# busanalizer.net
KiCad netlist of a schematic drawn in Altium Designer
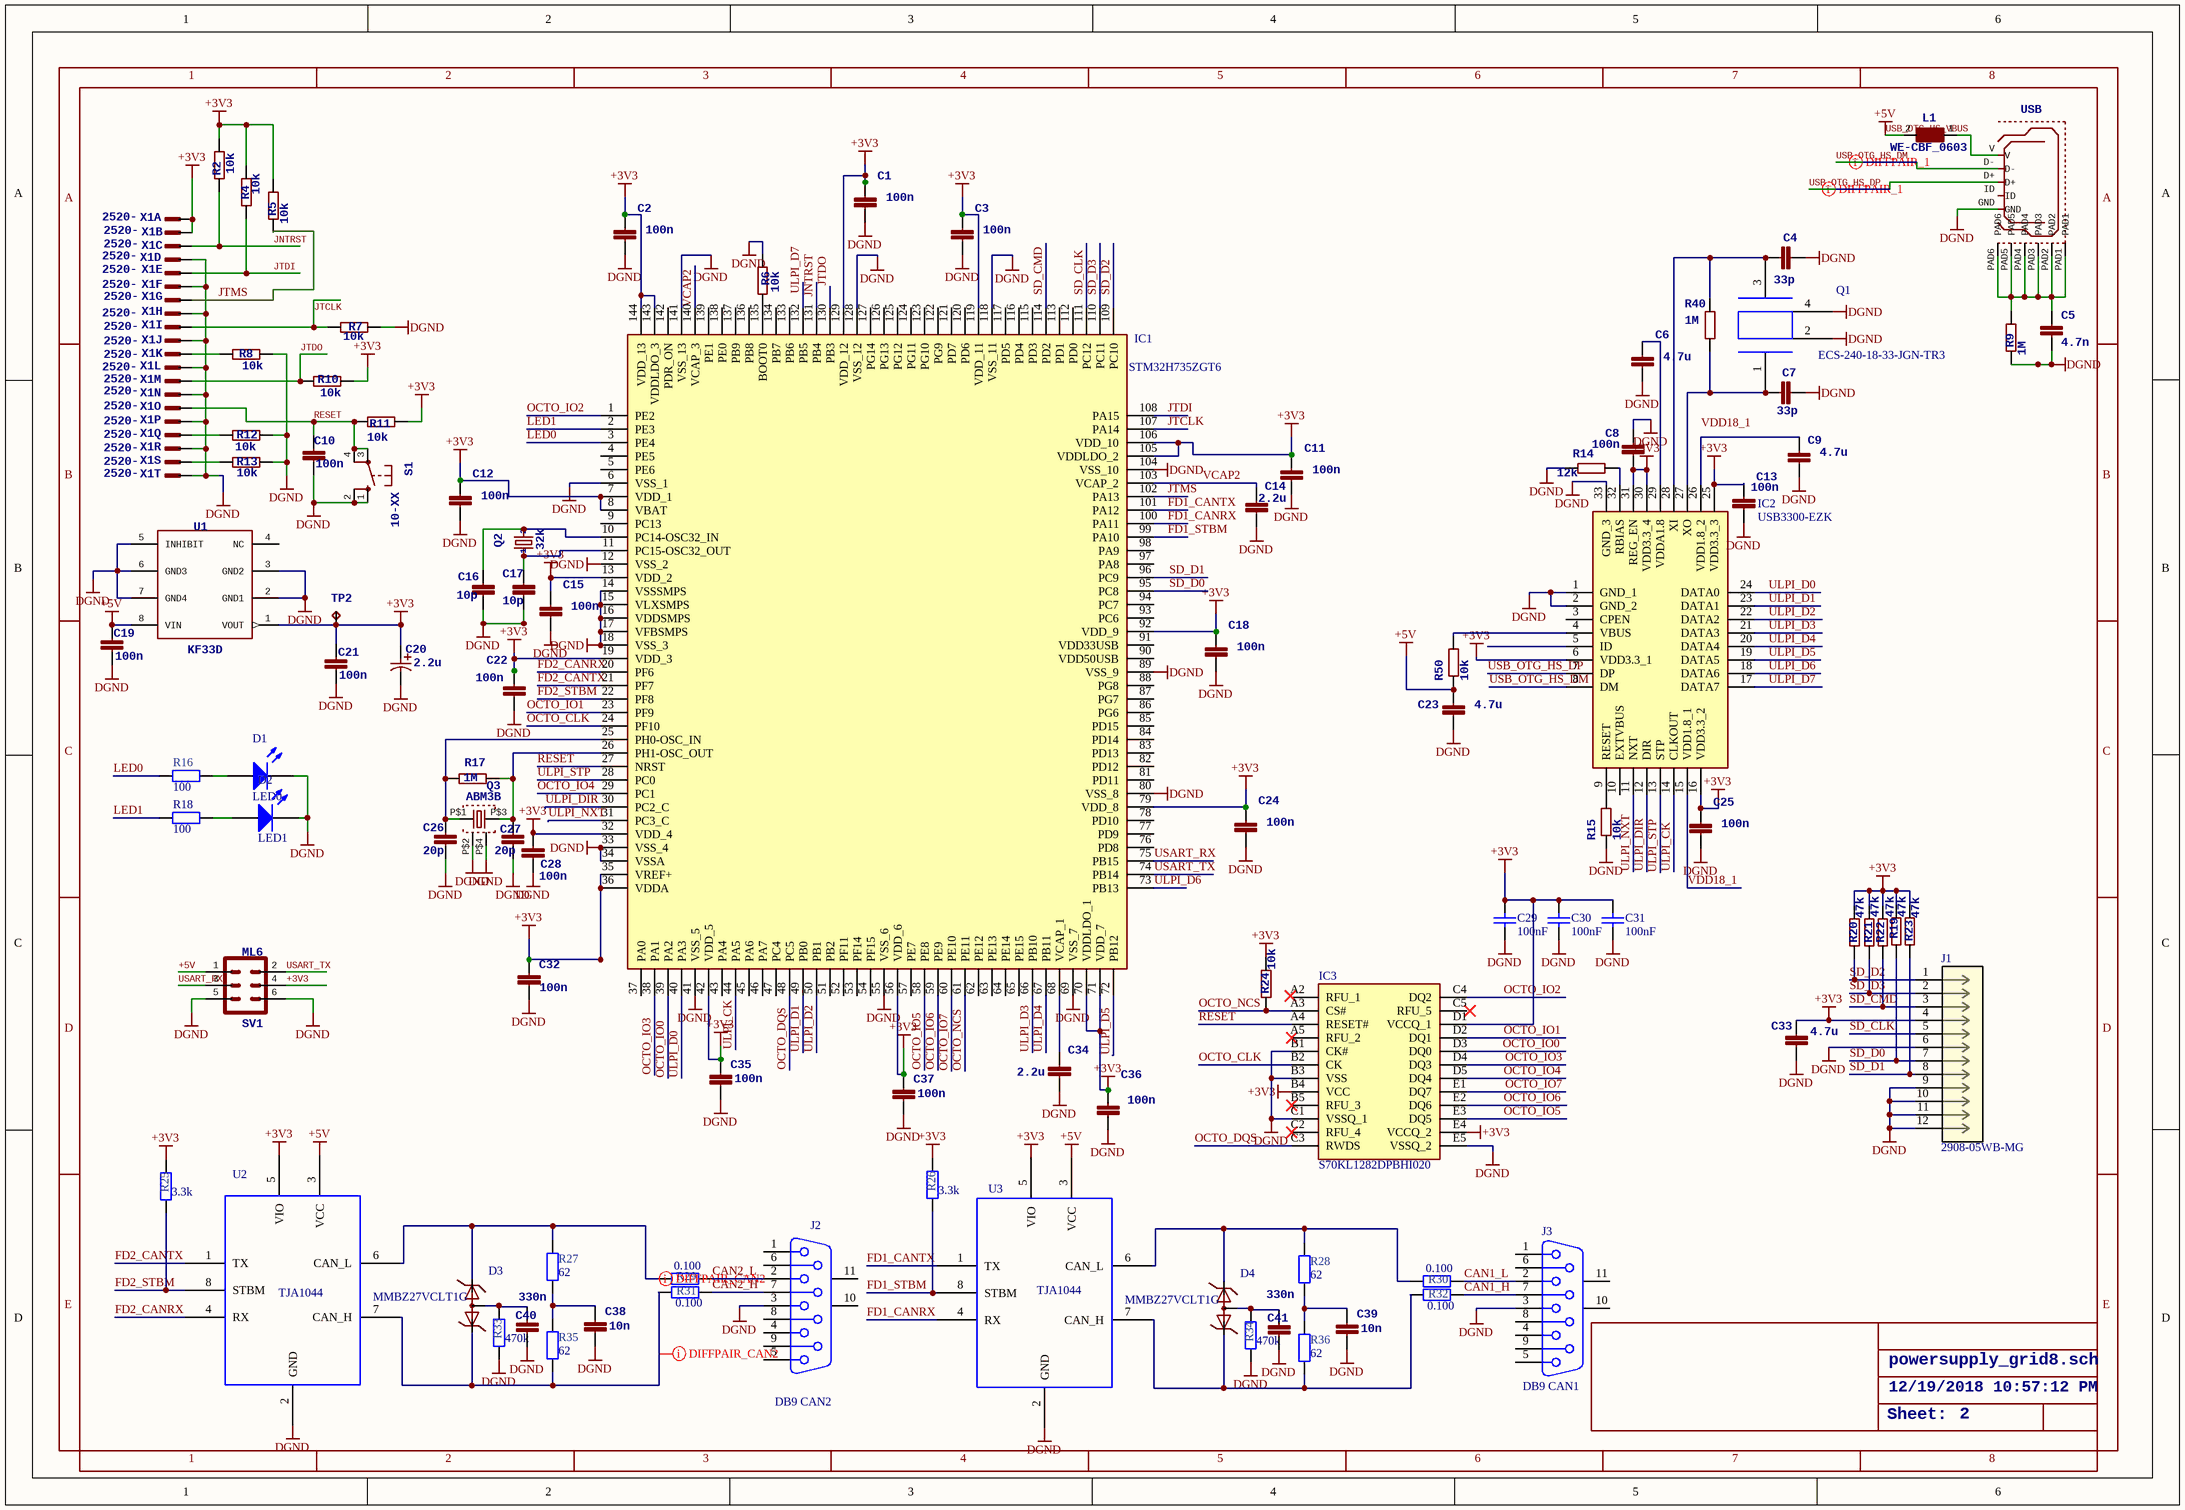
[diagram p0: busanalizer.SchDoc]

(export (version "E")
  (design (tool "Eeschema 10.0.6"))
  (components
    (comp (ref "C1")
      (value "100n")
      (footprint "C0402")
      (description "<B>CAPACITOR</B>, European symbol")
      (libsource (lib "rcl") (part "C-EUC0402"))
    )
    (comp (ref "C2")
      (value "100n")
      (footprint "C0402")
      (description "<B>CAPACITOR</B>, European symbol")
      (libsource (lib "rcl") (part "C-EUC0402"))
    )
    (comp (ref "C3")
      (value "100n")
      (footprint "C0402")
      (description "<B>CAPACITOR</B>, European symbol")
      (libsource (lib "rcl") (part "C-EUC0402"))
    )
    (comp (ref "C4")
      (value "33p")
      (footprint "C0402")
      (description "<B>CAPACITOR</B>, European symbol")
      (libsource (lib "") (part "C-EUC0402_1"))
    )
    (comp (ref "C5")
      (value "4.7n")
      (footprint "C0805")
      (description "<B>CAPACITOR</B>, European symbol")
      (libsource (lib "rcl") (part "C-EUC0805"))
    )
    (comp (ref "C6")
      (value "4.7u")
      (footprint "rcl:C0805")
      (description "<B>CAPACITOR</B>, European symbol")
      (libsource (lib "rcl") (part "C-EUC0402"))
    )
    (comp (ref "C7")
      (value "33p")
      (footprint "C0402")
      (description "<B>CAPACITOR</B>, European symbol")
      (libsource (lib "") (part "C-EUC0402_1"))
    )
    (comp (ref "C8")
      (value "100n")
      (footprint "C0402")
      (description "<B>CAPACITOR</B>, European symbol")
      (libsource (lib "") (part "C-EUC0402_2"))
    )
    (comp (ref "C9")
      (value "4.7u")
      (footprint "rcl:C0805")
      (description "<B>CAPACITOR</B>, European symbol")
      (libsource (lib "rcl") (part "C-EUC0402"))
    )
    (comp (ref "C10")
      (value "100n")
      (footprint "C0402")
      (description "<B>CAPACITOR</B>, European symbol")
      (libsource (lib "rcl") (part "C-EUC0402"))
    )
    (comp (ref "C11")
      (value "100n")
      (footprint "C0402")
      (description "<B>CAPACITOR</B>, European symbol")
      (libsource (lib "rcl") (part "C-EUC0402"))
    )
    (comp (ref "C12")
      (value "100n")
      (footprint "C0402")
      (description "<B>CAPACITOR</B>, European symbol")
      (libsource (lib "rcl") (part "C-EUC0402"))
    )
    (comp (ref "C13")
      (value "100n")
      (footprint "C0402")
      (description "<B>CAPACITOR</B>, European symbol")
      (libsource (lib "rcl") (part "C-EUC0402"))
    )
    (comp (ref "C14")
      (value "2.2u")
      (footprint "rcl:C0805")
      (description "<B>CAPACITOR</B>, European symbol")
      (libsource (lib "rcl") (part "C-EUC0402"))
    )
    (comp (ref "C15")
      (value "100n")
      (footprint "C0402")
      (description "<B>CAPACITOR</B>, European symbol")
      (libsource (lib "rcl") (part "C-EUC0402"))
    )
    (comp (ref "C16")
      (value "10p")
      (footprint "C0402")
      (description "<B>CAPACITOR</B>, European symbol")
      (libsource (lib "") (part "C-EUC0402_2"))
    )
    (comp (ref "C17")
      (value "10p")
      (footprint "C0402")
      (description "<B>CAPACITOR</B>, European symbol")
      (libsource (lib "") (part "C-EUC0402_2"))
    )
    (comp (ref "C18")
      (value "100n")
      (footprint "C0402")
      (description "<B>CAPACITOR</B>, European symbol")
      (libsource (lib "rcl") (part "C-EUC0402"))
    )
    (comp (ref "C19")
      (value "100n")
      (footprint "C0603")
      (description "<B>CAPACITOR</B>, European symbol")
      (libsource (lib "rcl") (part "C-EUC0603"))
    )
    (comp (ref "C20")
      (value "2.2u")
      (footprint "Panasonic-EEEFT_EEEH:CAPAE430X610N")
      (fields
        (field (name "MPN") "EEE-FT0J101AR")
        (field (name "TOLERANCE") "±20 %")
        (field (name "MPN_1") "EEE-FT1A680AR")
      )
      (libsource (lib "Panasonic-EEEFT_EEEH") (part "EEE--CASE-B"))
    )
    (comp (ref "C21")
      (value "100n")
      (footprint "C0603")
      (description "<B>CAPACITOR</B>, European symbol")
      (libsource (lib "rcl") (part "C-EUC0603"))
    )
    (comp (ref "C22")
      (value "100n")
      (footprint "C0402")
      (description "<B>CAPACITOR</B>, European symbol")
      (libsource (lib "rcl") (part "C-EUC0402"))
    )
    (comp (ref "C23")
      (value "4.7u")
      (footprint "rcl:C0805")
      (description "<B>CAPACITOR</B>, European symbol")
      (libsource (lib "rcl") (part "C-EUC0402"))
    )
    (comp (ref "C24")
      (value "100n")
      (footprint "C0402")
      (description "<B>CAPACITOR</B>, European symbol")
      (libsource (lib "rcl") (part "C-EUC0402"))
    )
    (comp (ref "C25")
      (value "100n")
      (footprint "C0402")
      (description "<B>CAPACITOR</B>, European symbol")
      (libsource (lib "rcl") (part "C-EUC0402"))
    )
    (comp (ref "C26")
      (value "20p")
      (footprint "C0402")
      (description "<B>CAPACITOR</B>, European symbol")
      (libsource (lib "rcl") (part "C-EUC0402"))
    )
    (comp (ref "C27")
      (value "20p")
      (footprint "C0402")
      (description "<B>CAPACITOR</B>, European symbol")
      (libsource (lib "rcl") (part "C-EUC0402"))
    )
    (comp (ref "C28")
      (value "100n")
      (footprint "C0402")
      (description "<B>CAPACITOR</B>, European symbol")
      (libsource (lib "rcl") (part "C-EUC0402"))
    )
    (comp (ref "C29")
      (value "100nF")
      (footprint "C0402")
      (description "Capacitor, MLCC, 100nF, 16V, X7R, 10%, 0402, T=0,5mm")
      (fields
        (field (name "INTERNAL_PART_NUMBER") "MCD-00102")
        (field (name "MANUFACTURER_PART_NUMBER") "CC0402KRX7R7BB104")
        (field (name "PROVIDED_BY") "SUBCO")
      )
      (libsource (lib "MCD_PARTS_database") (part "Capacitor"))
    )
    (comp (ref "C30")
      (value "100nF")
      (footprint "C0402")
      (description "Capacitor, MLCC, 100nF, 16V, X7R, 10%, 0402, T=0,5mm")
      (fields
        (field (name "INTERNAL_PART_NUMBER") "MCD-00102")
        (field (name "MANUFACTURER_PART_NUMBER") "CC0402KRX7R7BB104")
        (field (name "PROVIDED_BY") "SUBCO")
      )
      (libsource (lib "MCD_PARTS_database") (part "Capacitor"))
    )
    (comp (ref "C31")
      (value "100nF")
      (footprint "C0402")
      (description "Capacitor, MLCC, 100nF, 16V, X7R, 10%, 0402, T=0,5mm")
      (fields
        (field (name "INTERNAL_PART_NUMBER") "MCD-00102")
        (field (name "MANUFACTURER_PART_NUMBER") "CC0402KRX7R7BB104")
        (field (name "PROVIDED_BY") "SUBCO")
      )
      (libsource (lib "MCD_PARTS_database") (part "Capacitor"))
    )
    (comp (ref "C32")
      (value "100n")
      (footprint "C0402")
      (description "<B>CAPACITOR</B>, European symbol")
      (libsource (lib "rcl") (part "C-EUC0402"))
    )
    (comp (ref "C33")
      (value "4.7u")
      (footprint "rcl:C0805")
      (description "<B>CAPACITOR</B>, European symbol")
      (libsource (lib "rcl") (part "C-EUC0402"))
    )
    (comp (ref "C34")
      (value "2.2u")
      (footprint "rcl:C0805")
      (description "<B>CAPACITOR</B>, European symbol")
      (libsource (lib "rcl") (part "C-EUC0402"))
    )
    (comp (ref "C35")
      (value "100n")
      (footprint "C0402")
      (description "<B>CAPACITOR</B>, European symbol")
      (libsource (lib "rcl") (part "C-EUC0402"))
    )
    (comp (ref "C36")
      (value "100n")
      (footprint "C0402")
      (description "<B>CAPACITOR</B>, European symbol")
      (libsource (lib "rcl") (part "C-EUC0402"))
    )
    (comp (ref "C37")
      (value "100n")
      (footprint "C0402")
      (description "<B>CAPACITOR</B>, European symbol")
      (libsource (lib "rcl") (part "C-EUC0402"))
    )
    (comp (ref "C38")
      (value "10n")
      (footprint "C0805")
      (description "<B>CAPACITOR</B>, European symbol")
      (libsource (lib "rcl") (part "C-EUC0402"))
    )
    (comp (ref "C39")
      (value "10n")
      (footprint "C0805")
      (description "<B>CAPACITOR</B>, European symbol")
      (libsource (lib "rcl") (part "C-EUC0402"))
    )
    (comp (ref "C40")
      (value "330n")
      (footprint "C0805")
      (description "<B>CAPACITOR</B>, European symbol")
      (libsource (lib "rcl") (part "C-EUC0402"))
    )
    (comp (ref "C41")
      (value "330n")
      (footprint "C0805")
      (description "<B>CAPACITOR</B>, European symbol")
      (libsource (lib "rcl") (part "C-EUC0402"))
    )
    (comp (ref "D1")
      (value "LED0")
      (footprint "LED-0")
      (description "Typical INFRARED GaAs LED")
      (fields (field (name "PUBLISHER") "Altium Limited"))
      (libsource (lib "Miscellaneous Devices") (part "LED0"))
    )
    (comp (ref "D2")
      (value "LED1")
      (footprint "LED-0")
      (description "Typical INFRARED GaAs LED")
      (fields (field (name "PUBLISHER") "Altium Limited"))
      (libsource (lib "Miscellaneous Devices") (part "LED0"))
    )
    (comp (ref "D3")
      (value "MMBZ27VCLT1G")
      (footprint "SOT23")
      (libsource (lib "MMBZ27VCLT1G") (part "MMBZ27VCLT1G"))
    )
    (comp (ref "D4")
      (value "MMBZ27VCLT1G")
      (footprint "SOT23")
      (libsource (lib "MMBZ27VCLT1G") (part "MMBZ27VCLT1G"))
    )
    (comp (ref "IC1")
      (value "STM32H735ZGT6")
      (footprint "SamacSys:QFP50P2200X2200X160-144N")
      (description "Integrated Circuit")
      (libsource (lib "*") (part "STM32H735ZGT6"))
    )
    (comp (ref "IC2")
      (value "USB3300-EZK")
      (footprint "SamacSys:QFN50P500X500X100-33N-D")
      (description "Integrated Circuit")
      (fields (field (name "MOUSER2 PART NUMBER") "886-USB3300-EZK"))
      (libsource (lib "*") (part "USB3300-EZK"))
    )
    (comp (ref "IC3")
      (value "S70KL1282DPBHI020")
      (footprint "SamacSys:BGA24C100P5X5_600X800X100")
      (description "Integrated Circuit")
      (fields (field (name "MANUFACTURER_PART_NUMBER") "S70KL1281DABHI023"))
      (libsource (lib "*") (part "S70KL1281DABHI023"))
    )
    (comp (ref "J1")
      (value "2908-05WB-MG")
      (footprint "CONN_3M_2900")
      (description "No Description Available")
      (fields (field (name "COPYRIGHT") "Copyright (C) 2018 Accelerated Designs. All rights reserved"))
      (libsource (lib "2021-01-25_15-19-21") (part "2908-05WB-MG"))
    )
    (comp (ref "J2")
      (value "DB9 CAN2")
      (footprint "DSUB1.385-2H9")
      (description "Receptacle Assembly, 9 Position, Right Angle")
      (fields (field (name "PUBLISHER") "Altium Limited"))
      (libsource (lib "Miscellaneous Connectors") (part "D Connector 9"))
    )
    (comp (ref "J3")
      (value "DB9 CAN1")
      (footprint "DSUB1.385-2H9")
      (description "Receptacle Assembly, 9 Position, Right Angle")
      (fields (field (name "PUBLISHER") "Altium Limited"))
      (libsource (lib "Miscellaneous Connectors") (part "D Connector 9"))
    )
    (comp (ref "L1")
      (value "WE-CBF_0603")
      (footprint "WE-CBF:0603")
      (fields (field (name "MPN") "742792695"))
      (libsource (lib "WE-CBF") (part "WE-CBF_0603"))
    )
    (comp (ref "Q1")
      (value "ECS-240-18-33-JGN-TR3")
      (footprint "MCSJK-7U-24.00_1")
      (libsource (lib "MCSJK-7U-24.00") (part "MCSJK-7U-24.00_1"))
    )
    (comp (ref "Q2")
      (value "32k")
      (footprint "crystal:TC26V")
      (description "<b>CRYSTAL</b>")
      (fields (field (name "1") "1") (field (name "2") "2"))
      (libsource (lib "crystal") (part "CRYSTALTC26V"))
    )
    (comp (ref "Q3")
      (value "ABM3B")
      (footprint "crystal_my:ABM3B")
      (libsource (lib "crystal_my") (part "ABM3B"))
    )
    (comp (ref "R2")
      (value "10k")
      (footprint "R0805")
      (description "<B>RESISTOR</B>, European symbol")
      (libsource (lib "rcl") (part "R-EU_R0805"))
    )
    (comp (ref "R4")
      (value "10k")
      (footprint "R0805")
      (description "<B>RESISTOR</B>, European symbol")
      (libsource (lib "rcl") (part "R-EU_R0805"))
    )
    (comp (ref "R5")
      (value "10k")
      (footprint "R0805")
      (description "<B>RESISTOR</B>, European symbol")
      (libsource (lib "rcl") (part "R-EU_R0805"))
    )
    (comp (ref "R6")
      (value "10k")
      (footprint "R0805")
      (description "<B>RESISTOR</B>, European symbol")
      (libsource (lib "rcl") (part "R-EU_R0805"))
    )
    (comp (ref "R7")
      (value "10k")
      (footprint "R0805")
      (description "<B>RESISTOR</B>, European symbol")
      (libsource (lib "rcl") (part "R-EU_R0805"))
    )
    (comp (ref "R8")
      (value "10k")
      (footprint "R0805")
      (description "<B>RESISTOR</B>, European symbol")
      (libsource (lib "rcl") (part "R-EU_R0805"))
    )
    (comp (ref "R9")
      (value "1M")
      (footprint "R0805")
      (description "<B>RESISTOR</B>, European symbol")
      (libsource (lib "rcl") (part "R-EU_R0805"))
    )
    (comp (ref "R10")
      (value "10k")
      (footprint "R0805")
      (description "<B>RESISTOR</B>, European symbol")
      (libsource (lib "rcl") (part "R-EU_R0805"))
    )
    (comp (ref "R11")
      (value "10k")
      (footprint "R0805")
      (description "<B>RESISTOR</B>, European symbol")
      (libsource (lib "rcl") (part "R-EU_R0805"))
    )
    (comp (ref "R12")
      (value "10k")
      (footprint "R0805")
      (description "<B>RESISTOR</B>, European symbol")
      (libsource (lib "rcl") (part "R-EU_R0805"))
    )
    (comp (ref "R13")
      (value "10k")
      (footprint "R0805")
      (description "<B>RESISTOR</B>, European symbol")
      (libsource (lib "rcl") (part "R-EU_R0805"))
    )
    (comp (ref "R14") (value "12k") (footprint "R0805") (libsource (lib "rcl") (part "R-EU_R0805")))
    (comp (ref "R15") (value "10k") (footprint "R0805") (libsource (lib "rcl") (part "R-EU_R0805")))
    (comp (ref "R16")
      (value "100")
      (footprint "6-0805_L")
      (description "Resistor")
      (fields (field (name "Comment") "Res2") (field (name "PUBLISHER") "Altium Limited"))
      (libsource (lib "Miscellaneous Devices") (part "Res2"))
    )
    (comp (ref "R17")
      (value "1M")
      (footprint "R0402")
      (description "<B>RESISTOR</B>, European symbol")
      (libsource (lib "rcl") (part "R-EU_R0402"))
    )
    (comp (ref "R18")
      (value "100")
      (footprint "6-0805_L")
      (description "Resistor")
      (fields (field (name "Comment") "Res2") (field (name "PUBLISHER") "Altium Limited"))
      (libsource (lib "Miscellaneous Devices") (part "Res2"))
    )
    (comp (ref "R19")
      (value "47k")
      (footprint "R0805")
      (description "<B>RESISTOR</B>, European symbol")
      (libsource (lib "rcl") (part "R-EU_R0805"))
    )
    (comp (ref "R20")
      (value "47k")
      (footprint "R0805")
      (description "<B>RESISTOR</B>, European symbol")
      (libsource (lib "rcl") (part "R-EU_R0805"))
    )
    (comp (ref "R21")
      (value "47k")
      (footprint "R0805")
      (description "<B>RESISTOR</B>, European symbol")
      (libsource (lib "rcl") (part "R-EU_R0805"))
    )
    (comp (ref "R22")
      (value "47k")
      (footprint "R0805")
      (description "<B>RESISTOR</B>, European symbol")
      (libsource (lib "rcl") (part "R-EU_R0805"))
    )
    (comp (ref "R23")
      (value "47k")
      (footprint "R0805")
      (description "<B>RESISTOR</B>, European symbol")
      (libsource (lib "rcl") (part "R-EU_R0805"))
    )
    (comp (ref "R24")
      (value "10k")
      (footprint "R0805")
      (description "<B>RESISTOR</B>, European symbol")
      (libsource (lib "rcl") (part "R-EU_R0805"))
    )
    (comp (ref "R25")
      (value "3.3k")
      (footprint "R0805")
      (description "Resistor")
      (fields (field (name "Comment") "Res2") (field (name "PUBLISHER") "Altium Limited"))
      (libsource (lib "") (part "Res2_1"))
    )
    (comp (ref "R26")
      (value "3.3k")
      (footprint "R0805")
      (description "Resistor")
      (fields (field (name "Comment") "Res2") (field (name "PUBLISHER") "Altium Limited"))
      (libsource (lib "") (part "Res2_1"))
    )
    (comp (ref "R27")
      (value "62")
      (footprint "R0805")
      (description "Resistor")
      (fields (field (name "Comment") "Res2") (field (name "PUBLISHER") "Altium Limited"))
      (libsource (lib "") (part "Res2_1"))
    )
    (comp (ref "R28")
      (value "62")
      (footprint "R0805")
      (description "Resistor")
      (fields (field (name "Comment") "Res2") (field (name "PUBLISHER") "Altium Limited"))
      (libsource (lib "") (part "Res2_1"))
    )
    (comp (ref "R29")
      (value "0.100")
      (footprint "R0805")
      (description "Resistor")
      (fields (field (name "Comment") "Res2") (field (name "PUBLISHER") "Altium Limited"))
      (libsource (lib "Miscellaneous Devices") (part "Res2"))
    )
    (comp (ref "R30")
      (value "0.100")
      (footprint "R0805")
      (description "Resistor")
      (fields (field (name "Comment") "Res2") (field (name "PUBLISHER") "Altium Limited"))
      (libsource (lib "Miscellaneous Devices") (part "Res2"))
    )
    (comp (ref "R31")
      (value "0.100")
      (footprint "R0805")
      (description "Resistor")
      (fields (field (name "Comment") "Res2") (field (name "PUBLISHER") "Altium Limited"))
      (libsource (lib "Miscellaneous Devices") (part "Res2"))
    )
    (comp (ref "R32")
      (value "0.100")
      (footprint "R0805")
      (description "Resistor")
      (fields (field (name "Comment") "Res2") (field (name "PUBLISHER") "Altium Limited"))
      (libsource (lib "Miscellaneous Devices") (part "Res2"))
    )
    (comp (ref "R33")
      (value "470k")
      (footprint "R0805")
      (description "Resistor")
      (fields (field (name "Comment") "Res2") (field (name "PUBLISHER") "Altium Limited"))
      (libsource (lib "") (part "Res2_1"))
    )
    (comp (ref "R34")
      (value "470k")
      (footprint "R0805")
      (description "Resistor")
      (fields (field (name "Comment") "Res2") (field (name "PUBLISHER") "Altium Limited"))
      (libsource (lib "") (part "Res2_1"))
    )
    (comp (ref "R35")
      (value "62")
      (footprint "R0805")
      (description "Resistor")
      (fields (field (name "Comment") "Res2") (field (name "PUBLISHER") "Altium Limited"))
      (libsource (lib "") (part "Res2_1"))
    )
    (comp (ref "R36")
      (value "62")
      (footprint "R0805")
      (description "Resistor")
      (fields (field (name "Comment") "Res2") (field (name "PUBLISHER") "Altium Limited"))
      (libsource (lib "") (part "Res2_1"))
    )
    (comp (ref "R40") (value "1M") (footprint "R0805") (libsource (lib "rcl") (part "R-EU_R0805")))
    (comp (ref "R50") (value "10k") (footprint "R0805") (libsource (lib "rcl") (part "R-EU_R0805")))
    (comp (ref "S1")
      (value "10-XX")
      (footprint "switch-omron:B3F-10XX")
      (description "<b>OMRON SWITCH</b>")
      (fields (field (name "MPN") "B3F-1000"))
      (libsource (lib "switch-omron") (part "10-XX"))
    )
    (comp (ref "SV1")
      (value "ML6")
      (footprint "con-harting-ml:ML6")
      (description "<b>HARTING</b>")
      (libsource (lib "con-harting-ml") (part "ML6"))
    )
    (comp (ref "TP2")
      (value "TPB2,54")
      (footprint "B2,54")
      (description "<b>Test pad</b>")
      (libsource (lib "testpad") (part "TPB2,54"))
    )
    (comp (ref "U1") (value "KF33D") (footprint "KF33BD:SO8") (libsource (lib "KF33BD") (part "KF33D")))
    (comp (ref "U2") (value "TJA1044") (footprint "SO8") (libsource (lib "TJA1044") (part "TJA1044")))
    (comp (ref "U3") (value "TJA1044") (footprint "SO8") (libsource (lib "TJA1044") (part "TJA1044")))
    (comp (ref "USB1")
      (value "USB_MICROB")
      (footprint "usb_hinrose:USB_MICROB_PACKAGE")
      (description "This is the hirose ZX62-B-5PA(11) MICRO-USB B Type female connection.")
      (fields (field (name "USB") "USB"))
      (libsource (lib "usb_hinrose") (part "USB_MICROB"))
    )
    (comp (ref "X1")
      (value "2520-")
      (footprint "con-3m:PAK100/2500-20")
      (description "<b>3M (TM) Pak 100 4-Wall Header</b><p>\nSource: 3M")
      (libsource (lib "con-3m") (part "2520-"))
    )
  )
  (nets
    (net (code "1") (name "+3V3") (class "Default")
      (node (ref "C1") (pin "1") (pinfunction "1_1") (pintype "passive"))
      (node (ref "C11") (pin "1") (pinfunction "1_1") (pintype "passive"))
      (node (ref "C12") (pin "1") (pinfunction "1_1") (pintype "passive"))
      (node (ref "C13") (pin "1") (pinfunction "1_1") (pintype "passive"))
      (node (ref "C15") (pin "1") (pinfunction "1_1") (pintype "passive"))
      (node (ref "C18") (pin "1") (pinfunction "1_1") (pintype "passive"))
      (node (ref "C2") (pin "1") (pinfunction "1_1") (pintype "passive"))
      (node (ref "C20") (pin "1") (pinfunction "1_1") (pintype "passive"))
      (node (ref "C21") (pin "1") (pinfunction "1_1") (pintype "passive"))
      (node (ref "C22") (pin "1") (pinfunction "1_1") (pintype "passive"))
      (node (ref "C24") (pin "1") (pinfunction "1_1") (pintype "passive"))
      (node (ref "C25") (pin "1") (pinfunction "1_1") (pintype "passive"))
      (node (ref "C28") (pin "1") (pinfunction "1_1") (pintype "passive"))
      (node (ref "C29") (pin "2") (pinfunction "2_2") (pintype "passive"))
      (node (ref "C3") (pin "1") (pinfunction "1_1") (pintype "passive"))
      (node (ref "C30") (pin "2") (pinfunction "2_2") (pintype "passive"))
      (node (ref "C31") (pin "2") (pinfunction "2_2") (pintype "passive"))
      (node (ref "C32") (pin "1") (pinfunction "1_1") (pintype "passive"))
      (node (ref "C33") (pin "1") (pinfunction "1_1") (pintype "passive"))
      (node (ref "C35") (pin "1") (pinfunction "1_1") (pintype "passive"))
      (node (ref "C36") (pin "1") (pinfunction "1_1") (pintype "passive"))
      (node (ref "C37") (pin "1") (pinfunction "1_1") (pintype "passive"))
      (node (ref "C8") (pin "1") (pinfunction "1_1") (pintype "passive"))
      (node (ref "IC1") (pin "105") (pinfunction "VDDLDO_2_105") (pintype "passive"))
      (node (ref "IC1") (pin "106") (pinfunction "VDD_10_106") (pintype "passive"))
      (node (ref "IC1") (pin "119") (pinfunction "VDD_11_119") (pintype "passive"))
      (node (ref "IC1") (pin "129") (pinfunction "VDD_12_129") (pintype "passive"))
      (node (ref "IC1") (pin "13") (pinfunction "VDD_2_13") (pintype "passive"))
      (node (ref "IC1") (pin "143") (pinfunction "VDDLDO_3_143") (pintype "passive"))
      (node (ref "IC1") (pin "144") (pinfunction "VDD_13_144") (pintype "passive"))
      (node (ref "IC1") (pin "19") (pinfunction "VDD_3_19") (pintype "passive"))
      (node (ref "IC1") (pin "32") (pinfunction "VDD_4_32") (pintype "passive"))
      (node (ref "IC1") (pin "35") (pinfunction "VREF+_35") (pintype "passive"))
      (node (ref "IC1") (pin "36") (pinfunction "VDDA_36") (pintype "passive"))
      (node (ref "IC1") (pin "42") (pinfunction "VDD_5_42") (pintype "passive"))
      (node (ref "IC1") (pin "56") (pinfunction "VDD_6_56") (pintype "passive"))
      (node (ref "IC1") (pin "7") (pinfunction "VDD_1_7") (pintype "passive"))
      (node (ref "IC1") (pin "70") (pinfunction "VDDLDO_1_70") (pintype "passive"))
      (node (ref "IC1") (pin "71") (pinfunction "VDD_7_71") (pintype "passive"))
      (node (ref "IC1") (pin "79") (pinfunction "VDD_8_79") (pintype "passive"))
      (node (ref "IC1") (pin "8") (pinfunction "VBAT_8") (pintype "passive"))
      (node (ref "IC1") (pin "92") (pinfunction "VDD_9_92") (pintype "passive"))
      (node (ref "IC2") (pin "16") (pinfunction "VDD3.3_2_16") (pintype "passive"))
      (node (ref "IC2") (pin "25") (pinfunction "VDD3.3_3_25") (pintype "passive"))
      (node (ref "IC2") (pin "30") (pinfunction "VDD3.3_4_30") (pintype "passive"))
      (node (ref "IC2") (pin "31") (pinfunction "REG_EN_31") (pintype "passive"))
      (node (ref "IC2") (pin "6") (pinfunction "VDD3.3_1_6") (pintype "passive"))
      (node (ref "IC3") (pin "B4") (pinfunction "VCC_B4") (pintype "passive"))
      (node (ref "IC3") (pin "D1") (pinfunction "VCCQ_1_D1") (pintype "passive"))
      (node (ref "IC3") (pin "E4") (pinfunction "VCCQ_2_E4") (pintype "passive"))
      (node (ref "J1") (pin "4") (pinfunction "4_4") (pintype "passive"))
      (node (ref "R10") (pin "1") (pinfunction "1_1") (pintype "passive"))
      (node (ref "R11") (pin "1") (pinfunction "1_1") (pintype "passive"))
      (node (ref "R19") (pin "2") (pinfunction "2_2") (pintype "passive"))
      (node (ref "R2") (pin "2") (pinfunction "2_2") (pintype "passive"))
      (node (ref "R20") (pin "2") (pinfunction "2_2") (pintype "passive"))
      (node (ref "R21") (pin "2") (pinfunction "2_2") (pintype "passive"))
      (node (ref "R22") (pin "2") (pinfunction "2_2") (pintype "passive"))
      (node (ref "R23") (pin "2") (pinfunction "2_2") (pintype "passive"))
      (node (ref "R24") (pin "2") (pinfunction "2_2") (pintype "passive"))
      (node (ref "R25") (pin "2") (pinfunction "2_2") (pintype "passive"))
      (node (ref "R26") (pin "2") (pinfunction "2_2") (pintype "passive"))
      (node (ref "R4") (pin "2") (pinfunction "2_2") (pintype "passive"))
      (node (ref "R5") (pin "2") (pinfunction "2_2") (pintype "passive"))
      (node (ref "SV1") (pin "4") (pinfunction "4_4") (pintype "passive"))
      (node (ref "TP2") (pin "TP") (pinfunction "TP_TP") (pintype "passive"))
      (node (ref "U1") (pin "1") (pinfunction "VOUT_1") (pintype "output"))
      (node (ref "U2") (pin "5") (pinfunction "VIO_5") (pintype "passive"))
      (node (ref "U3") (pin "5") (pinfunction "VIO_5") (pintype "passive"))
      (node (ref "X1") (pin "1") (pinfunction "KL_1") (pintype "passive"))
      (node (ref "X1") (pin "2") (pinfunction "KL_2") (pintype "passive"))
    )
    (net (code "2") (name "+5V") (class "Default")
      (node (ref "C19") (pin "1") (pinfunction "1_1") (pintype "passive"))
      (node (ref "C23") (pin "1") (pinfunction "1_1") (pintype "passive"))
      (node (ref "L1") (pin "2") (pinfunction "2_2") (pintype "passive"))
      (node (ref "R50") (pin "1") (pinfunction "1_1") (pintype "passive"))
      (node (ref "SV1") (pin "1") (pinfunction "1_1") (pintype "passive"))
      (node (ref "U1") (pin "8") (pinfunction "VIN_8") (pintype "passive"))
      (node (ref "U2") (pin "3") (pinfunction "VCC_3") (pintype "passive"))
      (node (ref "U3") (pin "3") (pinfunction "VCC_3") (pintype "passive"))
    )
    (net (code "3") (name "/CAN1_H") (class "Default")
      (node (ref "J3") (pin "7") (pinfunction "7_7") (pintype "passive"))
      (node (ref "R32") (pin "2") (pinfunction "2_2") (pintype "passive"))
    )
    (net (code "4") (name "/CAN1_L") (class "Default")
      (node (ref "J3") (pin "2") (pinfunction "2_2") (pintype "passive"))
      (node (ref "R30") (pin "2") (pinfunction "2_2") (pintype "passive"))
    )
    (net (code "5") (name "/CAN2_H") (class "Default")
      (node (ref "J2") (pin "7") (pinfunction "7_7") (pintype "passive"))
      (node (ref "R31") (pin "2") (pinfunction "2_2") (pintype "passive"))
    )
    (net (code "6") (name "/CAN2_L") (class "Default")
      (node (ref "J2") (pin "2") (pinfunction "2_2") (pintype "passive"))
      (node (ref "R29") (pin "2") (pinfunction "2_2") (pintype "passive"))
    )
    (net (code "7") (name "/FD1_CANRX") (class "Default")
      (node (ref "IC1") (pin "100") (pinfunction "PA11_100") (pintype "passive"))
      (node (ref "U3") (pin "4") (pinfunction "RX_4") (pintype "passive"))
    )
    (net (code "8") (name "/FD1_CANTX") (class "Default")
      (node (ref "IC1") (pin "101") (pinfunction "PA12_101") (pintype "passive"))
      (node (ref "U3") (pin "1") (pinfunction "TX_1") (pintype "passive"))
    )
    (net (code "9") (name "/FD1_STBM") (class "Default")
      (node (ref "IC1") (pin "99") (pinfunction "PA10_99") (pintype "passive"))
      (node (ref "R26") (pin "1") (pinfunction "1_1") (pintype "passive"))
      (node (ref "U3") (pin "8") (pinfunction "STBM_8") (pintype "passive"))
    )
    (net (code "10") (name "/FD2_CANRX") (class "Default")
      (node (ref "IC1") (pin "20") (pinfunction "PF6_20") (pintype "passive"))
      (node (ref "U2") (pin "4") (pinfunction "RX_4") (pintype "passive"))
    )
    (net (code "11") (name "/FD2_CANTX") (class "Default")
      (node (ref "IC1") (pin "21") (pinfunction "PF7_21") (pintype "passive"))
      (node (ref "U2") (pin "1") (pinfunction "TX_1") (pintype "passive"))
    )
    (net (code "12") (name "/FD2_STBM") (class "Default")
      (node (ref "IC1") (pin "22") (pinfunction "PF8_22") (pintype "passive"))
      (node (ref "R25") (pin "1") (pinfunction "1_1") (pintype "passive"))
      (node (ref "U2") (pin "8") (pinfunction "STBM_8") (pintype "passive"))
    )
    (net (code "13") (name "/JNTRST") (class "Default")
      (node (ref "IC1") (pin "131") (pinfunction "PB4_131") (pintype "passive"))
      (node (ref "R2") (pin "1") (pinfunction "1_1") (pintype "passive"))
      (node (ref "X1") (pin "3") (pinfunction "KL_3") (pintype "passive"))
    )
    (net (code "14") (name "/JTCLK") (class "Default")
      (node (ref "IC1") (pin "107") (pinfunction "PA14_107") (pintype "passive"))
      (node (ref "R7") (pin "2") (pinfunction "2_2") (pintype "passive"))
      (node (ref "X1") (pin "9") (pinfunction "KL_9") (pintype "passive"))
    )
    (net (code "15") (name "/JTDI") (class "Default")
      (node (ref "IC1") (pin "108") (pinfunction "PA15_108") (pintype "passive"))
      (node (ref "R4") (pin "1") (pinfunction "1_1") (pintype "passive"))
      (node (ref "X1") (pin "5") (pinfunction "KL_5") (pintype "passive"))
    )
    (net (code "16") (name "/JTDO") (class "Default")
      (node (ref "IC1") (pin "130") (pinfunction "PB3_130") (pintype "passive"))
      (node (ref "R10") (pin "2") (pinfunction "2_2") (pintype "passive"))
      (node (ref "X1") (pin "13") (pinfunction "KL_13") (pintype "passive"))
    )
    (net (code "17") (name "/JTMS") (class "Default")
      (node (ref "IC1") (pin "102") (pinfunction "PA13_102") (pintype "passive"))
      (node (ref "R5") (pin "1") (pinfunction "1_1") (pintype "passive"))
      (node (ref "X1") (pin "7") (pinfunction "KL_7") (pintype "passive"))
    )
    (net (code "18") (name "/LED0") (class "Default")
      (node (ref "IC1") (pin "3") (pinfunction "PE4_3") (pintype "passive"))
      (node (ref "R16") (pin "1") (pinfunction "1_1") (pintype "passive"))
    )
    (net (code "19") (name "/LED1") (class "Default")
      (node (ref "IC1") (pin "2") (pinfunction "PE3_2") (pintype "passive"))
      (node (ref "R18") (pin "1") (pinfunction "1_1") (pintype "passive"))
    )
    (net (code "20") (name "/OCTO_CLK") (class "Default")
      (node (ref "IC1") (pin "24") (pinfunction "PF10_24") (pintype "passive"))
      (node (ref "IC3") (pin "B2") (pinfunction "CK_B2") (pintype "passive"))
    )
    (net (code "21") (name "/OCTO_DQS") (class "Default")
      (node (ref "IC1") (pin "48") (pinfunction "PC5_48") (pintype "passive"))
      (node (ref "IC3") (pin "C3") (pinfunction "RWDS_C3") (pintype "passive"))
    )
    (net (code "22") (name "/OCTO_IO0") (class "Default")
      (node (ref "IC1") (pin "39") (pinfunction "PA2_39") (pintype "passive"))
      (node (ref "IC3") (pin "D3") (pinfunction "DQ0_D3") (pintype "passive"))
    )
    (net (code "23") (name "/OCTO_IO1") (class "Default")
      (node (ref "IC1") (pin "23") (pinfunction "PF9_23") (pintype "passive"))
      (node (ref "IC3") (pin "D2") (pinfunction "DQ1_D2") (pintype "passive"))
    )
    (net (code "24") (name "/OCTO_IO2") (class "Default")
      (node (ref "IC1") (pin "1") (pinfunction "PE2_1") (pintype "passive"))
      (node (ref "IC3") (pin "C4") (pinfunction "DQ2_C4") (pintype "passive"))
    )
    (net (code "25") (name "/OCTO_IO3") (class "Default")
      (node (ref "IC1") (pin "38") (pinfunction "PA1_38") (pintype "passive"))
      (node (ref "IC3") (pin "D4") (pinfunction "DQ3_D4") (pintype "passive"))
    )
    (net (code "26") (name "/OCTO_IO4") (class "Default")
      (node (ref "IC1") (pin "29") (pinfunction "PC1_29") (pintype "passive"))
      (node (ref "IC3") (pin "D5") (pinfunction "DQ4_D5") (pintype "passive"))
    )
    (net (code "27") (name "/OCTO_IO5") (class "Default")
      (node (ref "IC1") (pin "58") (pinfunction "PE8_58") (pintype "passive"))
      (node (ref "IC3") (pin "E3") (pinfunction "DQ5_E3") (pintype "passive"))
    )
    (net (code "28") (name "/OCTO_IO6") (class "Default")
      (node (ref "IC1") (pin "59") (pinfunction "PE9_59") (pintype "passive"))
      (node (ref "IC3") (pin "E2") (pinfunction "DQ6_E2") (pintype "passive"))
    )
    (net (code "29") (name "/OCTO_IO7") (class "Default")
      (node (ref "IC1") (pin "60") (pinfunction "PE10_60") (pintype "passive"))
      (node (ref "IC3") (pin "E1") (pinfunction "DQ7_E1") (pintype "passive"))
    )
    (net (code "30") (name "/OCTO_NCS") (class "Default")
      (node (ref "IC1") (pin "61") (pinfunction "PE11_61") (pintype "passive"))
      (node (ref "IC3") (pin "A3") (pinfunction "CS#_A3") (pintype "passive"))
      (node (ref "R24") (pin "1") (pinfunction "1_1") (pintype "passive"))
    )
    (net (code "31") (name "/RESET") (class "Default")
      (node (ref "C10") (pin "1") (pinfunction "1_1") (pintype "passive"))
      (node (ref "IC1") (pin "27") (pinfunction "NRST_27") (pintype "passive"))
      (node (ref "IC3") (pin "A4") (pinfunction "RESET#_A4") (pintype "passive"))
      (node (ref "R11") (pin "2") (pinfunction "2_2") (pintype "passive"))
      (node (ref "S1") (pin "3") (pinfunction "P_3") (pintype "passive"))
      (node (ref "S1") (pin "4") (pinfunction "P1_4") (pintype "passive"))
      (node (ref "X1") (pin "15") (pinfunction "KL_15") (pintype "passive"))
    )
    (net (code "32") (name "/SD_CLK") (class "Default")
      (node (ref "IC1") (pin "111") (pinfunction "PC12_111") (pintype "passive"))
      (node (ref "J1") (pin "5") (pinfunction "5_5") (pintype "passive"))
    )
    (net (code "33") (name "/SD_CMD") (class "Default")
      (node (ref "IC1") (pin "114") (pinfunction "PD2_114") (pintype "passive"))
      (node (ref "J1") (pin "3") (pinfunction "3_3") (pintype "passive"))
      (node (ref "R22") (pin "1") (pinfunction "1_1") (pintype "passive"))
    )
    (net (code "34") (name "/SD_D0") (class "Default")
      (node (ref "IC1") (pin "95") (pinfunction "PC8_95") (pintype "passive"))
      (node (ref "J1") (pin "7") (pinfunction "7_7") (pintype "passive"))
      (node (ref "R19") (pin "1") (pinfunction "1_1") (pintype "passive"))
    )
    (net (code "35") (name "/SD_D1") (class "Default")
      (node (ref "IC1") (pin "96") (pinfunction "PC9_96") (pintype "passive"))
      (node (ref "J1") (pin "8") (pinfunction "8_8") (pintype "passive"))
      (node (ref "R23") (pin "1") (pinfunction "1_1") (pintype "passive"))
    )
    (net (code "36") (name "/SD_D2") (class "Default")
      (node (ref "IC1") (pin "109") (pinfunction "PC10_109") (pintype "passive"))
      (node (ref "J1") (pin "1") (pinfunction "1_1") (pintype "passive"))
      (node (ref "R20") (pin "1") (pinfunction "1_1") (pintype "passive"))
    )
    (net (code "37") (name "/SD_D3") (class "Default")
      (node (ref "IC1") (pin "110") (pinfunction "PC11_110") (pintype "passive"))
      (node (ref "J1") (pin "2") (pinfunction "2_2") (pintype "passive"))
      (node (ref "R21") (pin "1") (pinfunction "1_1") (pintype "passive"))
    )
    (net (code "38") (name "/ULPI_CK") (class "Default")
      (node (ref "IC1") (pin "44") (pinfunction "PA5_44") (pintype "passive"))
      (node (ref "IC2") (pin "14") (pinfunction "CLKOUT_14") (pintype "passive"))
    )
    (net (code "39") (name "/ULPI_D0") (class "Default")
      (node (ref "IC1") (pin "40") (pinfunction "PA3_40") (pintype "passive"))
      (node (ref "IC2") (pin "24") (pinfunction "DATA0_24") (pintype "passive"))
    )
    (net (code "40") (name "/ULPI_D1") (class "Default")
      (node (ref "IC1") (pin "49") (pinfunction "PB0_49") (pintype "passive"))
      (node (ref "IC2") (pin "23") (pinfunction "DATA1_23") (pintype "passive"))
    )
    (net (code "41") (name "/ULPI_D2") (class "Default")
      (node (ref "IC1") (pin "50") (pinfunction "PB1_50") (pintype "passive"))
      (node (ref "IC2") (pin "22") (pinfunction "DATA2_22") (pintype "passive"))
    )
    (net (code "42") (name "/ULPI_D3") (class "Default")
      (node (ref "IC1") (pin "66") (pinfunction "PB10_66") (pintype "passive"))
      (node (ref "IC2") (pin "21") (pinfunction "DATA3_21") (pintype "passive"))
    )
    (net (code "43") (name "/ULPI_D4") (class "Default")
      (node (ref "IC1") (pin "67") (pinfunction "PB11_67") (pintype "passive"))
      (node (ref "IC2") (pin "20") (pinfunction "DATA4_20") (pintype "passive"))
    )
    (net (code "44") (name "/ULPI_D5") (class "Default")
      (node (ref "IC1") (pin "72") (pinfunction "PB12_72") (pintype "passive"))
      (node (ref "IC2") (pin "19") (pinfunction "DATA5_19") (pintype "passive"))
    )
    (net (code "45") (name "/ULPI_D6") (class "Default")
      (node (ref "IC1") (pin "73") (pinfunction "PB13_73") (pintype "passive"))
      (node (ref "IC2") (pin "18") (pinfunction "DATA6_18") (pintype "passive"))
    )
    (net (code "46") (name "/ULPI_D7") (class "Default")
      (node (ref "IC1") (pin "132") (pinfunction "PB5_132") (pintype "passive"))
      (node (ref "IC2") (pin "17") (pinfunction "DATA7_17") (pintype "passive"))
    )
    (net (code "47") (name "/ULPI_DIR") (class "Default")
      (node (ref "IC1") (pin "30") (pinfunction "PC2_C_30") (pintype "passive"))
      (node (ref "IC2") (pin "12") (pinfunction "DIR_12") (pintype "passive"))
    )
    (net (code "48") (name "/ULPI_NXT") (class "Default")
      (node (ref "IC1") (pin "31") (pinfunction "PC3_C_31") (pintype "passive"))
      (node (ref "IC2") (pin "11") (pinfunction "NXT_11") (pintype "passive"))
    )
    (net (code "49") (name "/ULPI_STP") (class "Default")
      (node (ref "IC1") (pin "28") (pinfunction "PC0_28") (pintype "passive"))
      (node (ref "IC2") (pin "13") (pinfunction "STP_13") (pintype "passive"))
    )
    (net (code "50") (name "/USART_RX") (class "Default")
      (node (ref "IC1") (pin "75") (pinfunction "PB15_75") (pintype "passive"))
      (node (ref "SV1") (pin "3") (pinfunction "3_3") (pintype "passive"))
    )
    (net (code "51") (name "/USART_TX") (class "Default")
      (node (ref "IC1") (pin "74") (pinfunction "PB14_74") (pintype "passive"))
      (node (ref "SV1") (pin "2") (pinfunction "2_2") (pintype "passive"))
    )
    (net (code "52") (name "/USB_OTG_HS_DM") (class "Default")
      (node (ref "IC2") (pin "8") (pinfunction "DM_8") (pintype "passive"))
      (node (ref "USB1") (pin "D-") (pinfunction "D-_D-") (pintype "passive"))
    )
    (net (code "53") (name "/USB_OTG_HS_DP") (class "Default")
      (node (ref "IC2") (pin "7") (pinfunction "DP_7") (pintype "passive"))
      (node (ref "USB1") (pin "D+") (pinfunction "D+_D+") (pintype "passive"))
    )
    (net (code "54") (name "/VCAP2") (class "Default")
      (node (ref "C14") (pin "1") (pinfunction "1_1") (pintype "passive"))
      (node (ref "IC1") (pin "103") (pinfunction "VCAP_2_103") (pintype "passive"))
      (node (ref "IC1") (pin "140") (pinfunction "VCAP_3_140") (pintype "passive"))
    )
    (net (code "55") (name "/VDD18_1") (class "Default")
      (node (ref "IC2") (pin "15") (pinfunction "VDD1.8_1_15") (pintype "passive"))
    )
    (net (code "56") (name "DGND") (class "Default")
      (node (ref "C1") (pin "2") (pinfunction "2_2") (pintype "passive"))
      (node (ref "C10") (pin "2") (pinfunction "2_2") (pintype "passive"))
      (node (ref "C11") (pin "2") (pinfunction "2_2") (pintype "passive"))
      (node (ref "C12") (pin "2") (pinfunction "2_2") (pintype "passive"))
      (node (ref "C13") (pin "2") (pinfunction "2_2") (pintype "passive"))
      (node (ref "C14") (pin "2") (pinfunction "2_2") (pintype "passive"))
      (node (ref "C15") (pin "2") (pinfunction "2_2") (pintype "passive"))
      (node (ref "C16") (pin "1") (pinfunction "1_1") (pintype "passive"))
      (node (ref "C17") (pin "1") (pinfunction "1_1") (pintype "passive"))
      (node (ref "C18") (pin "2") (pinfunction "2_2") (pintype "passive"))
      (node (ref "C19") (pin "2") (pinfunction "2_2") (pintype "passive"))
      (node (ref "C2") (pin "2") (pinfunction "2_2") (pintype "passive"))
      (node (ref "C20") (pin "2") (pinfunction "2_2") (pintype "passive"))
      (node (ref "C21") (pin "2") (pinfunction "2_2") (pintype "passive"))
      (node (ref "C22") (pin "2") (pinfunction "2_2") (pintype "passive"))
      (node (ref "C23") (pin "2") (pinfunction "2_2") (pintype "passive"))
      (node (ref "C24") (pin "2") (pinfunction "2_2") (pintype "passive"))
      (node (ref "C25") (pin "2") (pinfunction "2_2") (pintype "passive"))
      (node (ref "C26") (pin "2") (pinfunction "2_2") (pintype "passive"))
      (node (ref "C27") (pin "2") (pinfunction "2_2") (pintype "passive"))
      (node (ref "C28") (pin "2") (pinfunction "2_2") (pintype "passive"))
      (node (ref "C29") (pin "1") (pinfunction "1_1") (pintype "passive"))
      (node (ref "C3") (pin "2") (pinfunction "2_2") (pintype "passive"))
      (node (ref "C30") (pin "1") (pinfunction "1_1") (pintype "passive"))
      (node (ref "C31") (pin "1") (pinfunction "1_1") (pintype "passive"))
      (node (ref "C32") (pin "2") (pinfunction "2_2") (pintype "passive"))
      (node (ref "C33") (pin "2") (pinfunction "2_2") (pintype "passive"))
      (node (ref "C34") (pin "2") (pinfunction "2_2") (pintype "passive"))
      (node (ref "C35") (pin "2") (pinfunction "2_2") (pintype "passive"))
      (node (ref "C36") (pin "2") (pinfunction "2_2") (pintype "passive"))
      (node (ref "C37") (pin "2") (pinfunction "2_2") (pintype "passive"))
      (node (ref "C38") (pin "2") (pinfunction "2_2") (pintype "passive"))
      (node (ref "C39") (pin "2") (pinfunction "2_2") (pintype "passive"))
      (node (ref "C4") (pin "1") (pinfunction "1_1") (pintype "passive"))
      (node (ref "C40") (pin "2") (pinfunction "2_2") (pintype "passive"))
      (node (ref "C41") (pin "2") (pinfunction "2_2") (pintype "passive"))
      (node (ref "C5") (pin "2") (pinfunction "2_2") (pintype "passive"))
      (node (ref "C6") (pin "2") (pinfunction "2_2") (pintype "passive"))
      (node (ref "C7") (pin "1") (pinfunction "1_1") (pintype "passive"))
      (node (ref "C8") (pin "2") (pinfunction "2_2") (pintype "passive"))
      (node (ref "C9") (pin "2") (pinfunction "2_2") (pintype "passive"))
      (node (ref "D1") (pin "2") (pinfunction "K_2") (pintype "passive"))
      (node (ref "D2") (pin "2") (pinfunction "K_2") (pintype "passive"))
      (node (ref "IC1") (pin "104") (pinfunction "VSS_10_104") (pintype "passive"))
      (node (ref "IC1") (pin "118") (pinfunction "VSS_11_118") (pintype "passive"))
      (node (ref "IC1") (pin "12") (pinfunction "VSS_2_12") (pintype "passive"))
      (node (ref "IC1") (pin "128") (pinfunction "VSS_12_128") (pintype "passive"))
      (node (ref "IC1") (pin "14") (pinfunction "VSSSMPS_14") (pintype "passive"))
      (node (ref "IC1") (pin "141") (pinfunction "VSS_13_141") (pintype "passive"))
      (node (ref "IC1") (pin "15") (pinfunction "VLXSMPS_15") (pintype "passive"))
      (node (ref "IC1") (pin "16") (pinfunction "VDDSMPS_16") (pintype "passive"))
      (node (ref "IC1") (pin "17") (pinfunction "VFBSMPS_17") (pintype "passive"))
      (node (ref "IC1") (pin "18") (pinfunction "VSS_3_18") (pintype "passive"))
      (node (ref "IC1") (pin "33") (pinfunction "VSS_4_33") (pintype "passive"))
      (node (ref "IC1") (pin "34") (pinfunction "VSSA_34") (pintype "passive"))
      (node (ref "IC1") (pin "41") (pinfunction "VSS_5_41") (pintype "passive"))
      (node (ref "IC1") (pin "55") (pinfunction "VSS_6_55") (pintype "passive"))
      (node (ref "IC1") (pin "6") (pinfunction "VSS_1_6") (pintype "passive"))
      (node (ref "IC1") (pin "69") (pinfunction "VSS_7_69") (pintype "passive"))
      (node (ref "IC1") (pin "80") (pinfunction "VSS_8_80") (pintype "passive"))
      (node (ref "IC1") (pin "89") (pinfunction "VSS_9_89") (pintype "passive"))
      (node (ref "IC2") (pin "1") (pinfunction "GND_1_1") (pintype "passive"))
      (node (ref "IC2") (pin "2") (pinfunction "GND_2_2") (pintype "passive"))
      (node (ref "IC2") (pin "33") (pinfunction "GND_3_33") (pintype "passive"))
      (node (ref "IC3") (pin "B1") (pinfunction "CK#_B1") (pintype "passive"))
      (node (ref "IC3") (pin "B3") (pinfunction "VSS_B3") (pintype "passive"))
      (node (ref "IC3") (pin "C1") (pinfunction "VSSQ_1_C1") (pintype "passive"))
      (node (ref "IC3") (pin "E5") (pinfunction "VSSQ_2_E5") (pintype "passive"))
      (node (ref "J1") (pin "10") (pinfunction "10_10") (pintype "passive"))
      (node (ref "J1") (pin "11") (pinfunction "11_11") (pintype "passive"))
      (node (ref "J1") (pin "12") (pinfunction "12_12") (pintype "passive"))
      (node (ref "J1") (pin "6") (pinfunction "6_6") (pintype "passive"))
      (node (ref "J1") (pin "9") (pinfunction "9_9") (pintype "passive"))
      (node (ref "J2") (pin "3") (pinfunction "3_3") (pintype "passive"))
      (node (ref "J3") (pin "3") (pinfunction "3_3") (pintype "passive"))
      (node (ref "Q1") (pin "2") (pintype "passive"))
      (node (ref "Q1") (pin "4") (pintype "passive"))
      (node (ref "Q3") (pin "P$2") (pinfunction "2_P$2") (pintype "passive"))
      (node (ref "Q3") (pin "P$4") (pinfunction "4_P$4") (pintype "passive"))
      (node (ref "R12") (pin "1") (pinfunction "1_1") (pintype "passive"))
      (node (ref "R13") (pin "1") (pinfunction "1_1") (pintype "passive"))
      (node (ref "R14") (pin "1") (pinfunction "1_1") (pintype "passive"))
      (node (ref "R15") (pin "1") (pinfunction "1_1") (pintype "passive"))
      (node (ref "R33") (pin "1") (pinfunction "1_1") (pintype "passive"))
      (node (ref "R34") (pin "1") (pinfunction "1_1") (pintype "passive"))
      (node (ref "R6") (pin "1") (pinfunction "1_1") (pintype "passive"))
      (node (ref "R7") (pin "1") (pinfunction "1_1") (pintype "passive"))
      (node (ref "R8") (pin "1") (pinfunction "1_1") (pintype "passive"))
      (node (ref "R9") (pin "1") (pinfunction "1_1") (pintype "passive"))
      (node (ref "S1") (pin "1") (pinfunction "S_1") (pintype "passive"))
      (node (ref "S1") (pin "2") (pinfunction "S1_2") (pintype "passive"))
      (node (ref "SV1") (pin "5") (pinfunction "5_5") (pintype "passive"))
      (node (ref "SV1") (pin "6") (pinfunction "6_6") (pintype "passive"))
      (node (ref "U1") (pin "2") (pinfunction "GND1_2") (pintype "power_in"))
      (node (ref "U1") (pin "3") (pinfunction "GND2_3") (pintype "power_in"))
      (node (ref "U1") (pin "5") (pinfunction "INHIBIT_5") (pintype "passive"))
      (node (ref "U1") (pin "6") (pinfunction "GND3_6") (pintype "power_in"))
      (node (ref "U1") (pin "7") (pinfunction "GND4_7") (pintype "power_in"))
      (node (ref "U2") (pin "2") (pinfunction "GND_2") (pintype "passive"))
      (node (ref "U3") (pin "2") (pinfunction "GND_2") (pintype "passive"))
      (node (ref "USB1") (pin "GND") (pinfunction "GND_GND") (pintype "passive"))
      (node (ref "X1") (pin "10") (pinfunction "KL_10") (pintype "passive"))
      (node (ref "X1") (pin "12") (pinfunction "KL_12") (pintype "passive"))
      (node (ref "X1") (pin "14") (pinfunction "KL_14") (pintype "passive"))
      (node (ref "X1") (pin "16") (pinfunction "KL_16") (pintype "passive"))
      (node (ref "X1") (pin "18") (pinfunction "KL_18") (pintype "passive"))
      (node (ref "X1") (pin "20") (pinfunction "KL_20") (pintype "passive"))
      (node (ref "X1") (pin "4") (pinfunction "KL_4") (pintype "passive"))
      (node (ref "X1") (pin "6") (pinfunction "KL_6") (pintype "passive"))
      (node (ref "X1") (pin "8") (pinfunction "KL_8") (pintype "passive"))
    )
    (net (code "57") (name "Net-(C5-Pad1)") (class "Default")
      (node (ref "C5") (pin "1") (pinfunction "1_1") (pintype "passive"))
      (node (ref "R9") (pin "2") (pinfunction "2_2") (pintype "passive"))
      (node (ref "USB1") (pin "PAD1") (pinfunction "PAD1_PAD1") (pintype "passive"))
      (node (ref "USB1") (pin "PAD2") (pinfunction "PAD2_PAD2") (pintype "passive"))
      (node (ref "USB1") (pin "PAD3") (pinfunction "PAD3_PAD3") (pintype "passive"))
      (node (ref "USB1") (pin "PAD4") (pinfunction "PAD4_PAD4") (pintype "passive"))
      (node (ref "USB1") (pin "PAD5") (pinfunction "PAD5_PAD5") (pintype "passive"))
      (node (ref "USB1") (pin "PAD6") (pinfunction "PAD6_PAD6") (pintype "passive"))
    )
    (net (code "58") (name "Net-(C38-Pad1)") (class "Default")
      (node (ref "C38") (pin "1") (pinfunction "1_1") (pintype "passive"))
      (node (ref "R27") (pin "1") (pinfunction "1_1") (pintype "passive"))
      (node (ref "R35") (pin "2") (pinfunction "2_2") (pintype "passive"))
    )
    (net (code "59") (name "Net-(C39-Pad1)") (class "Default")
      (node (ref "C39") (pin "1") (pinfunction "1_1") (pintype "passive"))
      (node (ref "R28") (pin "1") (pinfunction "1_1") (pintype "passive"))
      (node (ref "R36") (pin "2") (pinfunction "2_2") (pintype "passive"))
    )
    (net (code "60") (name "Net-(D1-A)") (class "Default")
      (node (ref "D1") (pin "1") (pinfunction "A_1") (pintype "passive"))
      (node (ref "R16") (pin "2") (pinfunction "2_2") (pintype "passive"))
    )
    (net (code "61") (name "Net-(D2-A)") (class "Default")
      (node (ref "D2") (pin "1") (pinfunction "A_1") (pintype "passive"))
      (node (ref "R18") (pin "2") (pinfunction "2_2") (pintype "passive"))
    )
    (net (code "62") (name "Net-(D3-A)") (class "Default")
      (node (ref "C40") (pin "1") (pinfunction "1_1") (pintype "passive"))
      (node (ref "D3") (pin "3") (pinfunction "A_3") (pintype "passive"))
      (node (ref "R33") (pin "2") (pinfunction "2_2") (pintype "passive"))
    )
    (net (code "63") (name "Net-(D3-K1)") (class "Default")
      (node (ref "D3") (pin "1") (pinfunction "K1_1") (pintype "passive"))
      (node (ref "R27") (pin "2") (pinfunction "2_2") (pintype "passive"))
      (node (ref "R29") (pin "1") (pinfunction "1_1") (pintype "passive"))
      (node (ref "U2") (pin "6") (pinfunction "CAN_L_6") (pintype "passive"))
    )
    (net (code "64") (name "Net-(D3-K2)") (class "Default")
      (node (ref "D3") (pin "2") (pinfunction "K2_2") (pintype "passive"))
      (node (ref "R31") (pin "1") (pinfunction "1_1") (pintype "passive"))
      (node (ref "R35") (pin "1") (pinfunction "1_1") (pintype "passive"))
      (node (ref "U2") (pin "7") (pinfunction "CAN_H_7") (pintype "passive"))
    )
    (net (code "65") (name "Net-(D4-A)") (class "Default")
      (node (ref "C41") (pin "1") (pinfunction "1_1") (pintype "passive"))
      (node (ref "D4") (pin "3") (pinfunction "A_3") (pintype "passive"))
      (node (ref "R34") (pin "2") (pinfunction "2_2") (pintype "passive"))
    )
    (net (code "66") (name "Net-(D4-K1)") (class "Default")
      (node (ref "D4") (pin "1") (pinfunction "K1_1") (pintype "passive"))
      (node (ref "R28") (pin "2") (pinfunction "2_2") (pintype "passive"))
      (node (ref "R30") (pin "1") (pinfunction "1_1") (pintype "passive"))
      (node (ref "U3") (pin "6") (pinfunction "CAN_L_6") (pintype "passive"))
    )
    (net (code "67") (name "Net-(D4-K2)") (class "Default")
      (node (ref "D4") (pin "2") (pinfunction "K2_2") (pintype "passive"))
      (node (ref "R32") (pin "1") (pinfunction "1_1") (pintype "passive"))
      (node (ref "R36") (pin "1") (pinfunction "1_1") (pintype "passive"))
      (node (ref "U3") (pin "7") (pinfunction "CAN_H_7") (pintype "passive"))
    )
    (net (code "68") (name "Net-(IC1-BOOT0)") (class "Default")
      (node (ref "IC1") (pin "135") (pinfunction "BOOT0_135") (pintype "passive"))
      (node (ref "R6") (pin "2") (pinfunction "2_2") (pintype "passive"))
    )
    (net (code "69") (name "Net-(IC1-PC14-OSC32_IN)") (class "Default")
      (node (ref "C16") (pin "2") (pinfunction "2_2") (pintype "passive"))
      (node (ref "IC1") (pin "10") (pinfunction "PC14-OSC32_IN_10") (pintype "passive"))
      (node (ref "Q2") (pin "2") (pinfunction "2_2") (pintype "passive"))
    )
    (net (code "70") (name "Net-(IC1-PC15-OSC32_OUT)") (class "Default")
      (node (ref "C17") (pin "2") (pinfunction "2_2") (pintype "passive"))
      (node (ref "IC1") (pin "11") (pinfunction "PC15-OSC32_OUT_11") (pintype "passive"))
      (node (ref "Q2") (pin "1") (pinfunction "1_1") (pintype "passive"))
    )
    (net (code "71") (name "Net-(IC1-PH0-OSC_IN)") (class "Default")
      (node (ref "C26") (pin "1") (pinfunction "1_1") (pintype "passive"))
      (node (ref "IC1") (pin "25") (pinfunction "PH0-OSC_IN_25") (pintype "passive"))
      (node (ref "Q3") (pin "P$1") (pinfunction "1_P$1") (pintype "passive"))
      (node (ref "R17") (pin "2") (pinfunction "2_2") (pintype "passive"))
    )
    (net (code "72") (name "Net-(IC1-PH1-OSC_OUT)") (class "Default")
      (node (ref "C27") (pin "1") (pinfunction "1_1") (pintype "passive"))
      (node (ref "IC1") (pin "26") (pinfunction "PH1-OSC_OUT_26") (pintype "passive"))
      (node (ref "Q3") (pin "P$3") (pinfunction "3_P$3") (pintype "passive"))
      (node (ref "R17") (pin "1") (pinfunction "1_1") (pintype "passive"))
    )
    (net (code "73") (name "Net-(IC1-VCAP_1)") (class "Default")
      (node (ref "C34") (pin "1") (pinfunction "1_1") (pintype "passive"))
      (node (ref "IC1") (pin "68") (pinfunction "VCAP_1_68") (pintype "passive"))
    )
    (net (code "74") (name "Net-(IC2-RBIAS)") (class "Default")
      (node (ref "IC2") (pin "32") (pinfunction "RBIAS_32") (pintype "passive"))
      (node (ref "R14") (pin "2") (pinfunction "2_2") (pintype "passive"))
    )
    (net (code "75") (name "Net-(IC2-RESET)") (class "Default")
      (node (ref "IC2") (pin "9") (pinfunction "RESET_9") (pintype "passive"))
      (node (ref "R15") (pin "2") (pinfunction "2_2") (pintype "passive"))
    )
    (net (code "76") (name "Net-(IC2-VBUS)") (class "Default")
      (node (ref "IC2") (pin "4") (pinfunction "VBUS_4") (pintype "passive"))
      (node (ref "R50") (pin "2") (pinfunction "2_2") (pintype "passive"))
    )
    (net (code "77") (name "Net-(IC2-VDD1.8_2)") (class "Default")
      (node (ref "C9") (pin "1") (pinfunction "1_1") (pintype "passive"))
      (node (ref "IC2") (pin "26") (pinfunction "VDD1.8_2_26") (pintype "passive"))
    )
    (net (code "78") (name "Net-(IC2-VDDA1.8)") (class "Default")
      (node (ref "C6") (pin "1") (pinfunction "1_1") (pintype "passive"))
      (node (ref "IC2") (pin "29") (pinfunction "VDDA1.8_29") (pintype "passive"))
    )
    (net (code "79") (name "Net-(IC2-XI)") (class "Default")
      (node (ref "C4") (pin "2") (pinfunction "2_2") (pintype "passive"))
      (node (ref "IC2") (pin "28") (pinfunction "XI_28") (pintype "passive"))
      (node (ref "Q1") (pin "3") (pintype "power_in"))
      (node (ref "R40") (pin "2") (pinfunction "2_2") (pintype "passive"))
    )
    (net (code "80") (name "Net-(IC2-XO)") (class "Default")
      (node (ref "C7") (pin "2") (pinfunction "2_2") (pintype "passive"))
      (node (ref "IC2") (pin "27") (pinfunction "XO_27") (pintype "passive"))
      (node (ref "Q1") (pin "1") (pintype "power_in"))
      (node (ref "R40") (pin "1") (pinfunction "1_1") (pintype "passive"))
    )
    (net (code "81") (name "Net-(L1-Pad1)") (class "Default")
      (node (ref "L1") (pin "1") (pinfunction "1_1") (pintype "passive"))
      (node (ref "USB1") (pin "V") (pinfunction "V_V") (pintype "passive"))
    )
    (net (code "82") (name "Net-(X1K-KL)") (class "Default")
      (node (ref "R8") (pin "2") (pinfunction "2_2") (pintype "passive"))
      (node (ref "X1") (pin "11") (pinfunction "KL_11") (pintype "passive"))
    )
    (net (code "83") (name "Net-(X1Q-KL)") (class "Default")
      (node (ref "R12") (pin "2") (pinfunction "2_2") (pintype "passive"))
      (node (ref "X1") (pin "17") (pinfunction "KL_17") (pintype "passive"))
    )
    (net (code "84") (name "Net-(X1S-KL)") (class "Default")
      (node (ref "R13") (pin "2") (pinfunction "2_2") (pintype "passive"))
      (node (ref "X1") (pin "19") (pinfunction "KL_19") (pintype "passive"))
    )
    (net (code "85") (name "unconnected-(IC1-PA0-Pad37)") (class "Default")
      (node (ref "IC1") (pin "37") (pinfunction "PA0_37") (pintype "passive"))
    )
    (net (code "86") (name "unconnected-(IC1-PA4-Pad43)") (class "Default")
      (node (ref "IC1") (pin "43") (pinfunction "PA4_43") (pintype "passive"))
    )
    (net (code "87") (name "unconnected-(IC1-PA6-Pad45)") (class "Default")
      (node (ref "IC1") (pin "45") (pinfunction "PA6_45") (pintype "passive"))
    )
    (net (code "88") (name "unconnected-(IC1-PA7-Pad46)") (class "Default")
      (node (ref "IC1") (pin "46") (pinfunction "PA7_46") (pintype "passive"))
    )
    (net (code "89") (name "unconnected-(IC1-PA8-Pad97)") (class "Default")
      (node (ref "IC1") (pin "97") (pinfunction "PA8_97") (pintype "passive"))
    )
    (net (code "90") (name "unconnected-(IC1-PA9-Pad98)") (class "Default")
      (node (ref "IC1") (pin "98") (pinfunction "PA9_98") (pintype "passive"))
    )
    (net (code "91") (name "unconnected-(IC1-PB2-Pad51)") (class "Default")
      (node (ref "IC1") (pin "51") (pinfunction "PB2_51") (pintype "passive"))
    )
    (net (code "92") (name "unconnected-(IC1-PB6-Pad133)") (class "Default")
      (node (ref "IC1") (pin "133") (pinfunction "PB6_133") (pintype "passive"))
    )
    (net (code "93") (name "unconnected-(IC1-PB7-Pad134)") (class "Default")
      (node (ref "IC1") (pin "134") (pinfunction "PB7_134") (pintype "passive"))
    )
    (net (code "94") (name "unconnected-(IC1-PB8-Pad136)") (class "Default")
      (node (ref "IC1") (pin "136") (pinfunction "PB8_136") (pintype "passive"))
    )
    (net (code "95") (name "unconnected-(IC1-PB9-Pad137)") (class "Default")
      (node (ref "IC1") (pin "137") (pinfunction "PB9_137") (pintype "passive"))
    )
    (net (code "96") (name "unconnected-(IC1-PC4-Pad47)") (class "Default")
      (node (ref "IC1") (pin "47") (pinfunction "PC4_47") (pintype "passive"))
    )
    (net (code "97") (name "unconnected-(IC1-PC6-Pad93)") (class "Default")
      (node (ref "IC1") (pin "93") (pinfunction "PC6_93") (pintype "passive"))
    )
    (net (code "98") (name "unconnected-(IC1-PC7-Pad94)") (class "Default")
      (node (ref "IC1") (pin "94") (pinfunction "PC7_94") (pintype "passive"))
    )
    (net (code "99") (name "unconnected-(IC1-PC13-Pad9)") (class "Default")
      (node (ref "IC1") (pin "9") (pinfunction "PC13_9") (pintype "passive"))
    )
    (net (code "100") (name "unconnected-(IC1-PD0-Pad112)") (class "Default")
      (node (ref "IC1") (pin "112") (pinfunction "PD0_112") (pintype "passive"))
    )
    (net (code "101") (name "unconnected-(IC1-PD1-Pad113)") (class "Default")
      (node (ref "IC1") (pin "113") (pinfunction "PD1_113") (pintype "passive"))
    )
    (net (code "102") (name "unconnected-(IC1-PD3-Pad115)") (class "Default")
      (node (ref "IC1") (pin "115") (pinfunction "PD3_115") (pintype "passive"))
    )
    (net (code "103") (name "unconnected-(IC1-PD4-Pad116)") (class "Default")
      (node (ref "IC1") (pin "116") (pinfunction "PD4_116") (pintype "passive"))
    )
    (net (code "104") (name "unconnected-(IC1-PD5-Pad117)") (class "Default")
      (node (ref "IC1") (pin "117") (pinfunction "PD5_117") (pintype "passive"))
    )
    (net (code "105") (name "unconnected-(IC1-PD6-Pad120)") (class "Default")
      (node (ref "IC1") (pin "120") (pinfunction "PD6_120") (pintype "passive"))
    )
    (net (code "106") (name "unconnected-(IC1-PD7-Pad121)") (class "Default")
      (node (ref "IC1") (pin "121") (pinfunction "PD7_121") (pintype "passive"))
    )
    (net (code "107") (name "unconnected-(IC1-PD8-Pad76)") (class "Default")
      (node (ref "IC1") (pin "76") (pinfunction "PD8_76") (pintype "passive"))
    )
    (net (code "108") (name "unconnected-(IC1-PD9-Pad77)") (class "Default")
      (node (ref "IC1") (pin "77") (pinfunction "PD9_77") (pintype "passive"))
    )
    (net (code "109") (name "unconnected-(IC1-PD10-Pad78)") (class "Default")
      (node (ref "IC1") (pin "78") (pinfunction "PD10_78") (pintype "passive"))
    )
    (net (code "110") (name "unconnected-(IC1-PD11-Pad81)") (class "Default")
      (node (ref "IC1") (pin "81") (pinfunction "PD11_81") (pintype "passive"))
    )
    (net (code "111") (name "unconnected-(IC1-PD12-Pad82)") (class "Default")
      (node (ref "IC1") (pin "82") (pinfunction "PD12_82") (pintype "passive"))
    )
    (net (code "112") (name "unconnected-(IC1-PD13-Pad83)") (class "Default")
      (node (ref "IC1") (pin "83") (pinfunction "PD13_83") (pintype "passive"))
    )
    (net (code "113") (name "unconnected-(IC1-PD14-Pad84)") (class "Default")
      (node (ref "IC1") (pin "84") (pinfunction "PD14_84") (pintype "passive"))
    )
    (net (code "114") (name "unconnected-(IC1-PD15-Pad85)") (class "Default")
      (node (ref "IC1") (pin "85") (pinfunction "PD15_85") (pintype "passive"))
    )
    (net (code "115") (name "unconnected-(IC1-PDR_ON-Pad142)") (class "Default")
      (node (ref "IC1") (pin "142") (pinfunction "PDR_ON_142") (pintype "passive"))
    )
    (net (code "116") (name "unconnected-(IC1-PE0-Pad138)") (class "Default")
      (node (ref "IC1") (pin "138") (pinfunction "PE0_138") (pintype "passive"))
    )
    (net (code "117") (name "unconnected-(IC1-PE1-Pad139)") (class "Default")
      (node (ref "IC1") (pin "139") (pinfunction "PE1_139") (pintype "passive"))
    )
    (net (code "118") (name "unconnected-(IC1-PE5-Pad4)") (class "Default")
      (node (ref "IC1") (pin "4") (pinfunction "PE5_4") (pintype "passive"))
    )
    (net (code "119") (name "unconnected-(IC1-PE6-Pad5)") (class "Default")
      (node (ref "IC1") (pin "5") (pinfunction "PE6_5") (pintype "passive"))
    )
    (net (code "120") (name "unconnected-(IC1-PE7-Pad57)") (class "Default")
      (node (ref "IC1") (pin "57") (pinfunction "PE7_57") (pintype "passive"))
    )
    (net (code "121") (name "unconnected-(IC1-PE12-Pad62)") (class "Default")
      (node (ref "IC1") (pin "62") (pinfunction "PE12_62") (pintype "passive"))
    )
    (net (code "122") (name "unconnected-(IC1-PE13-Pad63)") (class "Default")
      (node (ref "IC1") (pin "63") (pinfunction "PE13_63") (pintype "passive"))
    )
    (net (code "123") (name "unconnected-(IC1-PE14-Pad64)") (class "Default")
      (node (ref "IC1") (pin "64") (pinfunction "PE14_64") (pintype "passive"))
    )
    (net (code "124") (name "unconnected-(IC1-PE15-Pad65)") (class "Default")
      (node (ref "IC1") (pin "65") (pinfunction "PE15_65") (pintype "passive"))
    )
    (net (code "125") (name "unconnected-(IC1-PF11-Pad52)") (class "Default")
      (node (ref "IC1") (pin "52") (pinfunction "PF11_52") (pintype "passive"))
    )
    (net (code "126") (name "unconnected-(IC1-PF14-Pad53)") (class "Default")
      (node (ref "IC1") (pin "53") (pinfunction "PF14_53") (pintype "passive"))
    )
    (net (code "127") (name "unconnected-(IC1-PF15-Pad54)") (class "Default")
      (node (ref "IC1") (pin "54") (pinfunction "PF15_54") (pintype "passive"))
    )
    (net (code "128") (name "unconnected-(IC1-PG6-Pad86)") (class "Default")
      (node (ref "IC1") (pin "86") (pinfunction "PG6_86") (pintype "passive"))
    )
    (net (code "129") (name "unconnected-(IC1-PG7-Pad87)") (class "Default")
      (node (ref "IC1") (pin "87") (pinfunction "PG7_87") (pintype "passive"))
    )
    (net (code "130") (name "unconnected-(IC1-PG8-Pad88)") (class "Default")
      (node (ref "IC1") (pin "88") (pinfunction "PG8_88") (pintype "passive"))
    )
    (net (code "131") (name "unconnected-(IC1-PG9-Pad122)") (class "Default")
      (node (ref "IC1") (pin "122") (pinfunction "PG9_122") (pintype "passive"))
    )
    (net (code "132") (name "unconnected-(IC1-PG10-Pad123)") (class "Default")
      (node (ref "IC1") (pin "123") (pinfunction "PG10_123") (pintype "passive"))
    )
    (net (code "133") (name "unconnected-(IC1-PG11-Pad124)") (class "Default")
      (node (ref "IC1") (pin "124") (pinfunction "PG11_124") (pintype "passive"))
    )
    (net (code "134") (name "unconnected-(IC1-PG12-Pad125)") (class "Default")
      (node (ref "IC1") (pin "125") (pinfunction "PG12_125") (pintype "passive"))
    )
    (net (code "135") (name "unconnected-(IC1-PG13-Pad126)") (class "Default")
      (node (ref "IC1") (pin "126") (pinfunction "PG13_126") (pintype "passive"))
    )
    (net (code "136") (name "unconnected-(IC1-PG14-Pad127)") (class "Default")
      (node (ref "IC1") (pin "127") (pinfunction "PG14_127") (pintype "passive"))
    )
    (net (code "137") (name "unconnected-(IC1-VDD33USB-Pad91)") (class "Default")
      (node (ref "IC1") (pin "91") (pinfunction "VDD33USB_91") (pintype "passive"))
    )
    (net (code "138") (name "unconnected-(IC1-VDD50USB-Pad90)") (class "Default")
      (node (ref "IC1") (pin "90") (pinfunction "VDD50USB_90") (pintype "passive"))
    )
    (net (code "139") (name "unconnected-(IC2-CPEN-Pad3)") (class "Default")
      (node (ref "IC2") (pin "3") (pinfunction "CPEN_3") (pintype "passive"))
    )
    (net (code "140") (name "unconnected-(IC2-EXTVBUS-Pad10)") (class "Default")
      (node (ref "IC2") (pin "10") (pinfunction "EXTVBUS_10") (pintype "passive"))
    )
    (net (code "141") (name "unconnected-(IC2-ID-Pad5)") (class "Default")
      (node (ref "IC2") (pin "5") (pinfunction "ID_5") (pintype "passive"))
    )
    (net (code "142") (name "unconnected-(IC3-RFU_1-PadA2)") (class "Default")
      (node (ref "IC3") (pin "A2") (pinfunction "RFU_1_A2") (pintype "passive"))
    )
    (net (code "143") (name "unconnected-(IC3-RFU_2-PadA5)") (class "Default")
      (node (ref "IC3") (pin "A5") (pinfunction "RFU_2_A5") (pintype "passive+no_connect"))
    )
    (net (code "144") (name "unconnected-(IC3-RFU_3-PadB5)") (class "Default")
      (node (ref "IC3") (pin "B5") (pinfunction "RFU_3_B5") (pintype "passive+no_connect"))
    )
    (net (code "145") (name "unconnected-(IC3-RFU_4-PadC2)") (class "Default")
      (node (ref "IC3") (pin "C2") (pinfunction "RFU_4_C2") (pintype "passive+no_connect"))
    )
    (net (code "146") (name "unconnected-(IC3-RFU_5-PadC5)") (class "Default")
      (node (ref "IC3") (pin "C5") (pinfunction "RFU_5_C5") (pintype "passive"))
    )
    (net (code "147") (name "unconnected-(J2-MH1-Pad10)") (class "Default")
      (node (ref "J2") (pin "10") (pinfunction "MH1_10") (pintype "passive"))
    )
    (net (code "148") (name "unconnected-(J2-MH2-Pad11)") (class "Default")
      (node (ref "J2") (pin "11") (pinfunction "MH2_11") (pintype "passive"))
    )
    (net (code "149") (name "unconnected-(J2-Pad1)") (class "Default")
      (node (ref "J2") (pin "1") (pinfunction "1_1") (pintype "passive"))
    )
    (net (code "150") (name "unconnected-(J2-Pad4)") (class "Default")
      (node (ref "J2") (pin "4") (pinfunction "4_4") (pintype "passive"))
    )
    (net (code "151") (name "unconnected-(J2-Pad5)") (class "Default")
      (node (ref "J2") (pin "5") (pinfunction "5_5") (pintype "passive"))
    )
    (net (code "152") (name "unconnected-(J2-Pad6)") (class "Default")
      (node (ref "J2") (pin "6") (pinfunction "6_6") (pintype "passive"))
    )
    (net (code "153") (name "unconnected-(J2-Pad8)") (class "Default")
      (node (ref "J2") (pin "8") (pinfunction "8_8") (pintype "passive"))
    )
    (net (code "154") (name "unconnected-(J2-Pad9)") (class "Default")
      (node (ref "J2") (pin "9") (pinfunction "9_9") (pintype "passive"))
    )
    (net (code "155") (name "unconnected-(J3-MH1-Pad10)") (class "Default")
      (node (ref "J3") (pin "10") (pinfunction "MH1_10") (pintype "passive"))
    )
    (net (code "156") (name "unconnected-(J3-MH2-Pad11)") (class "Default")
      (node (ref "J3") (pin "11") (pinfunction "MH2_11") (pintype "passive"))
    )
    (net (code "157") (name "unconnected-(J3-Pad1)") (class "Default")
      (node (ref "J3") (pin "1") (pinfunction "1_1") (pintype "passive"))
    )
    (net (code "158") (name "unconnected-(J3-Pad4)") (class "Default")
      (node (ref "J3") (pin "4") (pinfunction "4_4") (pintype "passive"))
    )
    (net (code "159") (name "unconnected-(J3-Pad5)") (class "Default")
      (node (ref "J3") (pin "5") (pinfunction "5_5") (pintype "passive"))
    )
    (net (code "160") (name "unconnected-(J3-Pad6)") (class "Default")
      (node (ref "J3") (pin "6") (pinfunction "6_6") (pintype "passive"))
    )
    (net (code "161") (name "unconnected-(J3-Pad8)") (class "Default")
      (node (ref "J3") (pin "8") (pinfunction "8_8") (pintype "passive"))
    )
    (net (code "162") (name "unconnected-(J3-Pad9)") (class "Default")
      (node (ref "J3") (pin "9") (pinfunction "9_9") (pintype "passive"))
    )
    (net (code "163") (name "unconnected-(U1-NC-Pad4)") (class "Default")
      (node (ref "U1") (pin "4") (pinfunction "NC_4") (pintype "passive"))
    )
    (net (code "164") (name "unconnected-(USB1-PadID)") (class "Default")
      (node (ref "USB1") (pin "ID") (pinfunction "ID_ID") (pintype "passive"))
    )
  )
)
